# TopShem.net
KiCad netlist of a schematic drawn in Altium Designer
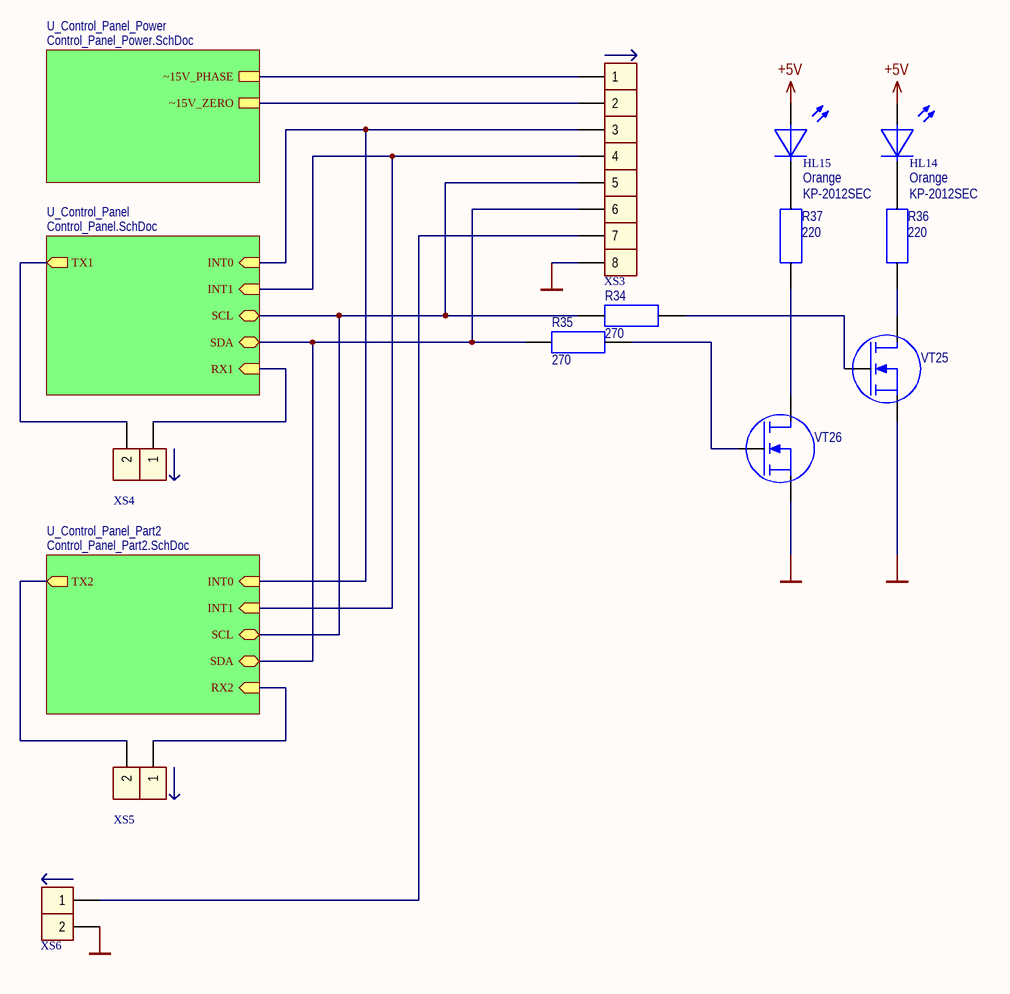
[diagram p0: TopShem.SchDoc]

(export (version "E")
  (design (tool "Eeschema 10.0.6"))
  (components
    (comp (ref "HL14")
      (value "Orange")
      (footprint "Indicator:DIOMELF2012M")
      (description "Diod LED SMD Orange")
      (fields (field (name "MANUFACTURERPARTNUMBER") "KP-2012SEC"))
      (libsource (lib "Indicator") (part "LED1_O"))
    )
    (comp (ref "HL15")
      (value "Orange")
      (footprint "Indicator:DIOMELF2012M")
      (description "Diod LED SMD Orange")
      (fields (field (name "MANUFACTURERPARTNUMBER") "KP-2012SEC"))
      (libsource (lib "Indicator") (part "LED1_O"))
    )
    (comp (ref "R34")
      (value "270")
      (footprint "SMDRC0805")
      (description "Generic resistor")
      (fields (field (name "PARTNUMBER") "Resistor 0805 270"))
      (libsource (lib "library") (part "Resistor"))
    )
    (comp (ref "R35")
      (value "270")
      (footprint "SMDRC0805")
      (description "Generic resistor")
      (fields (field (name "PARTNUMBER") "Resistor 0805 270"))
      (libsource (lib "library") (part "Resistor"))
    )
    (comp (ref "R36")
      (value "220")
      (footprint "SMDRC0805")
      (description "Generic resistor")
      (fields (field (name "PARTNUMBER") "Resistor 0805 220"))
      (libsource (lib "") (part "Resistor_1"))
    )
    (comp (ref "R37")
      (value "220")
      (footprint "SMDRC0805")
      (description "Generic resistor")
      (fields (field (name "PARTNUMBER") "Resistor 0805 220"))
      (libsource (lib "") (part "Resistor_1"))
    )
    (comp (ref "VT25")
      (value "2N7002")
      (footprint "Standard:SOT23 (TO-236AB)")
      (description "60V, 300mA N-channel Trench MOSFET")
      (libsource (lib "Transistor") (part "2N7002 n-MOSFET"))
    )
    (comp (ref "VT26")
      (value "2N7002")
      (footprint "Standard:SOT23 (TO-236AB)")
      (description "60V, 300mA N-channel Trench MOSFET")
      (libsource (lib "Transistor") (part "2N7002 n-MOSFET"))
    )
    (comp (ref "XS3")
      (value "PLS-08R")
      (footprint "Connector:PLS-08R2")
      (description "Male 8-pin connection")
      (libsource (lib "Connector") (part "Con8_M PLS-08MR"))
    )
    (comp (ref "XS4")
      (value "PLS-02")
      (footprint "Connector:PLS-02")
      (description "Male 2-pin connection")
      (libsource (lib "Connector") (part "Con2_M_PLS-02"))
    )
    (comp (ref "XS5")
      (value "PLS-02")
      (footprint "Connector:PLS-02")
      (description "Male 2-pin connection")
      (libsource (lib "Connector") (part "Con2_M_PLS-02"))
    )
    (comp (ref "XS6")
      (value "PLS-02R")
      (footprint "Connector:PLS-02R1")
      (description "Male 2-pin connection")
      (libsource (lib "Connector") (part "Con2_M_PLS-02R"))
    )
  )
  (nets
    (net (code "1") (name "+5V") (class "Default")
      (node (ref "HL14") (pin "1") (pinfunction "1_1") (pintype "passive"))
      (node (ref "HL15") (pin "1") (pinfunction "1_1") (pintype "passive"))
    )
    (net (code "2") (name "/INT0") (class "Default")
      (node (ref "XS3") (pin "3") (pinfunction "3_3") (pintype "passive"))
    )
    (net (code "3") (name "/INT1") (class "Default")
      (node (ref "XS3") (pin "4") (pinfunction "4_4") (pintype "passive"))
    )
    (net (code "4") (name "/RX1") (class "Default")
      (node (ref "XS4") (pin "1") (pinfunction "1_1") (pintype "passive"))
    )
    (net (code "5") (name "/RX2") (class "Default")
      (node (ref "XS5") (pin "1") (pinfunction "1_1") (pintype "passive"))
    )
    (net (code "6") (name "/SCL") (class "Default")
      (node (ref "R34") (pin "2") (pinfunction "2_2") (pintype "passive"))
      (node (ref "XS3") (pin "5") (pinfunction "5_5") (pintype "passive"))
    )
    (net (code "7") (name "/SDA") (class "Default")
      (node (ref "R35") (pin "2") (pinfunction "2_2") (pintype "passive"))
      (node (ref "XS3") (pin "6") (pinfunction "6_6") (pintype "passive"))
    )
    (net (code "8") (name "/TX1") (class "Default")
      (node (ref "XS4") (pin "2") (pinfunction "2_2") (pintype "passive"))
    )
    (net (code "9") (name "/TX2") (class "Default")
      (node (ref "XS5") (pin "2") (pinfunction "2_2") (pintype "passive"))
    )
    (net (code "10") (name "/~15V_PHASE") (class "Default")
      (node (ref "XS3") (pin "1") (pinfunction "1_1") (pintype "passive"))
    )
    (net (code "11") (name "/~15V_ZERO") (class "Default")
      (node (ref "XS3") (pin "2") (pinfunction "2_2") (pintype "passive"))
    )
    (net (code "12") (name "GND") (class "Default")
      (node (ref "VT25") (pin "2") (pinfunction "S_2") (pintype "passive"))
      (node (ref "VT26") (pin "2") (pinfunction "S_2") (pintype "passive"))
      (node (ref "XS3") (pin "8") (pinfunction "8_8") (pintype "passive"))
      (node (ref "XS6") (pin "2") (pinfunction "2_2") (pintype "passive"))
    )
    (net (code "13") (name "Net-(HL14-Pad2)") (class "Default")
      (node (ref "HL14") (pin "2") (pinfunction "2_2") (pintype "passive"))
      (node (ref "R36") (pin "2") (pinfunction "2_2") (pintype "passive"))
    )
    (net (code "14") (name "Net-(HL15-Pad2)") (class "Default")
      (node (ref "HL15") (pin "2") (pinfunction "2_2") (pintype "passive"))
      (node (ref "R37") (pin "2") (pinfunction "2_2") (pintype "passive"))
    )
    (net (code "15") (name "Net-(VT25-D)") (class "Default")
      (node (ref "R36") (pin "1") (pinfunction "1_1") (pintype "passive"))
      (node (ref "VT25") (pin "3") (pinfunction "D_3") (pintype "passive"))
    )
    (net (code "16") (name "Net-(VT25-G)") (class "Default")
      (node (ref "R34") (pin "1") (pinfunction "1_1") (pintype "passive"))
      (node (ref "VT25") (pin "1") (pinfunction "G_1") (pintype "passive"))
    )
    (net (code "17") (name "Net-(VT26-D)") (class "Default")
      (node (ref "R37") (pin "1") (pinfunction "1_1") (pintype "passive"))
      (node (ref "VT26") (pin "3") (pinfunction "D_3") (pintype "passive"))
    )
    (net (code "18") (name "Net-(VT26-G)") (class "Default")
      (node (ref "R35") (pin "1") (pinfunction "1_1") (pintype "passive"))
      (node (ref "VT26") (pin "1") (pinfunction "G_1") (pintype "passive"))
    )
    (net (code "19") (name "Net-(XS3-Pad7)") (class "Default")
      (node (ref "XS3") (pin "7") (pinfunction "7_7") (pintype "passive"))
      (node (ref "XS6") (pin "1") (pinfunction "1_1") (pintype "passive"))
    )
  )
)
